# 01_MCU_Interface.net
KiCad netlist of a schematic drawn in Altium Designer
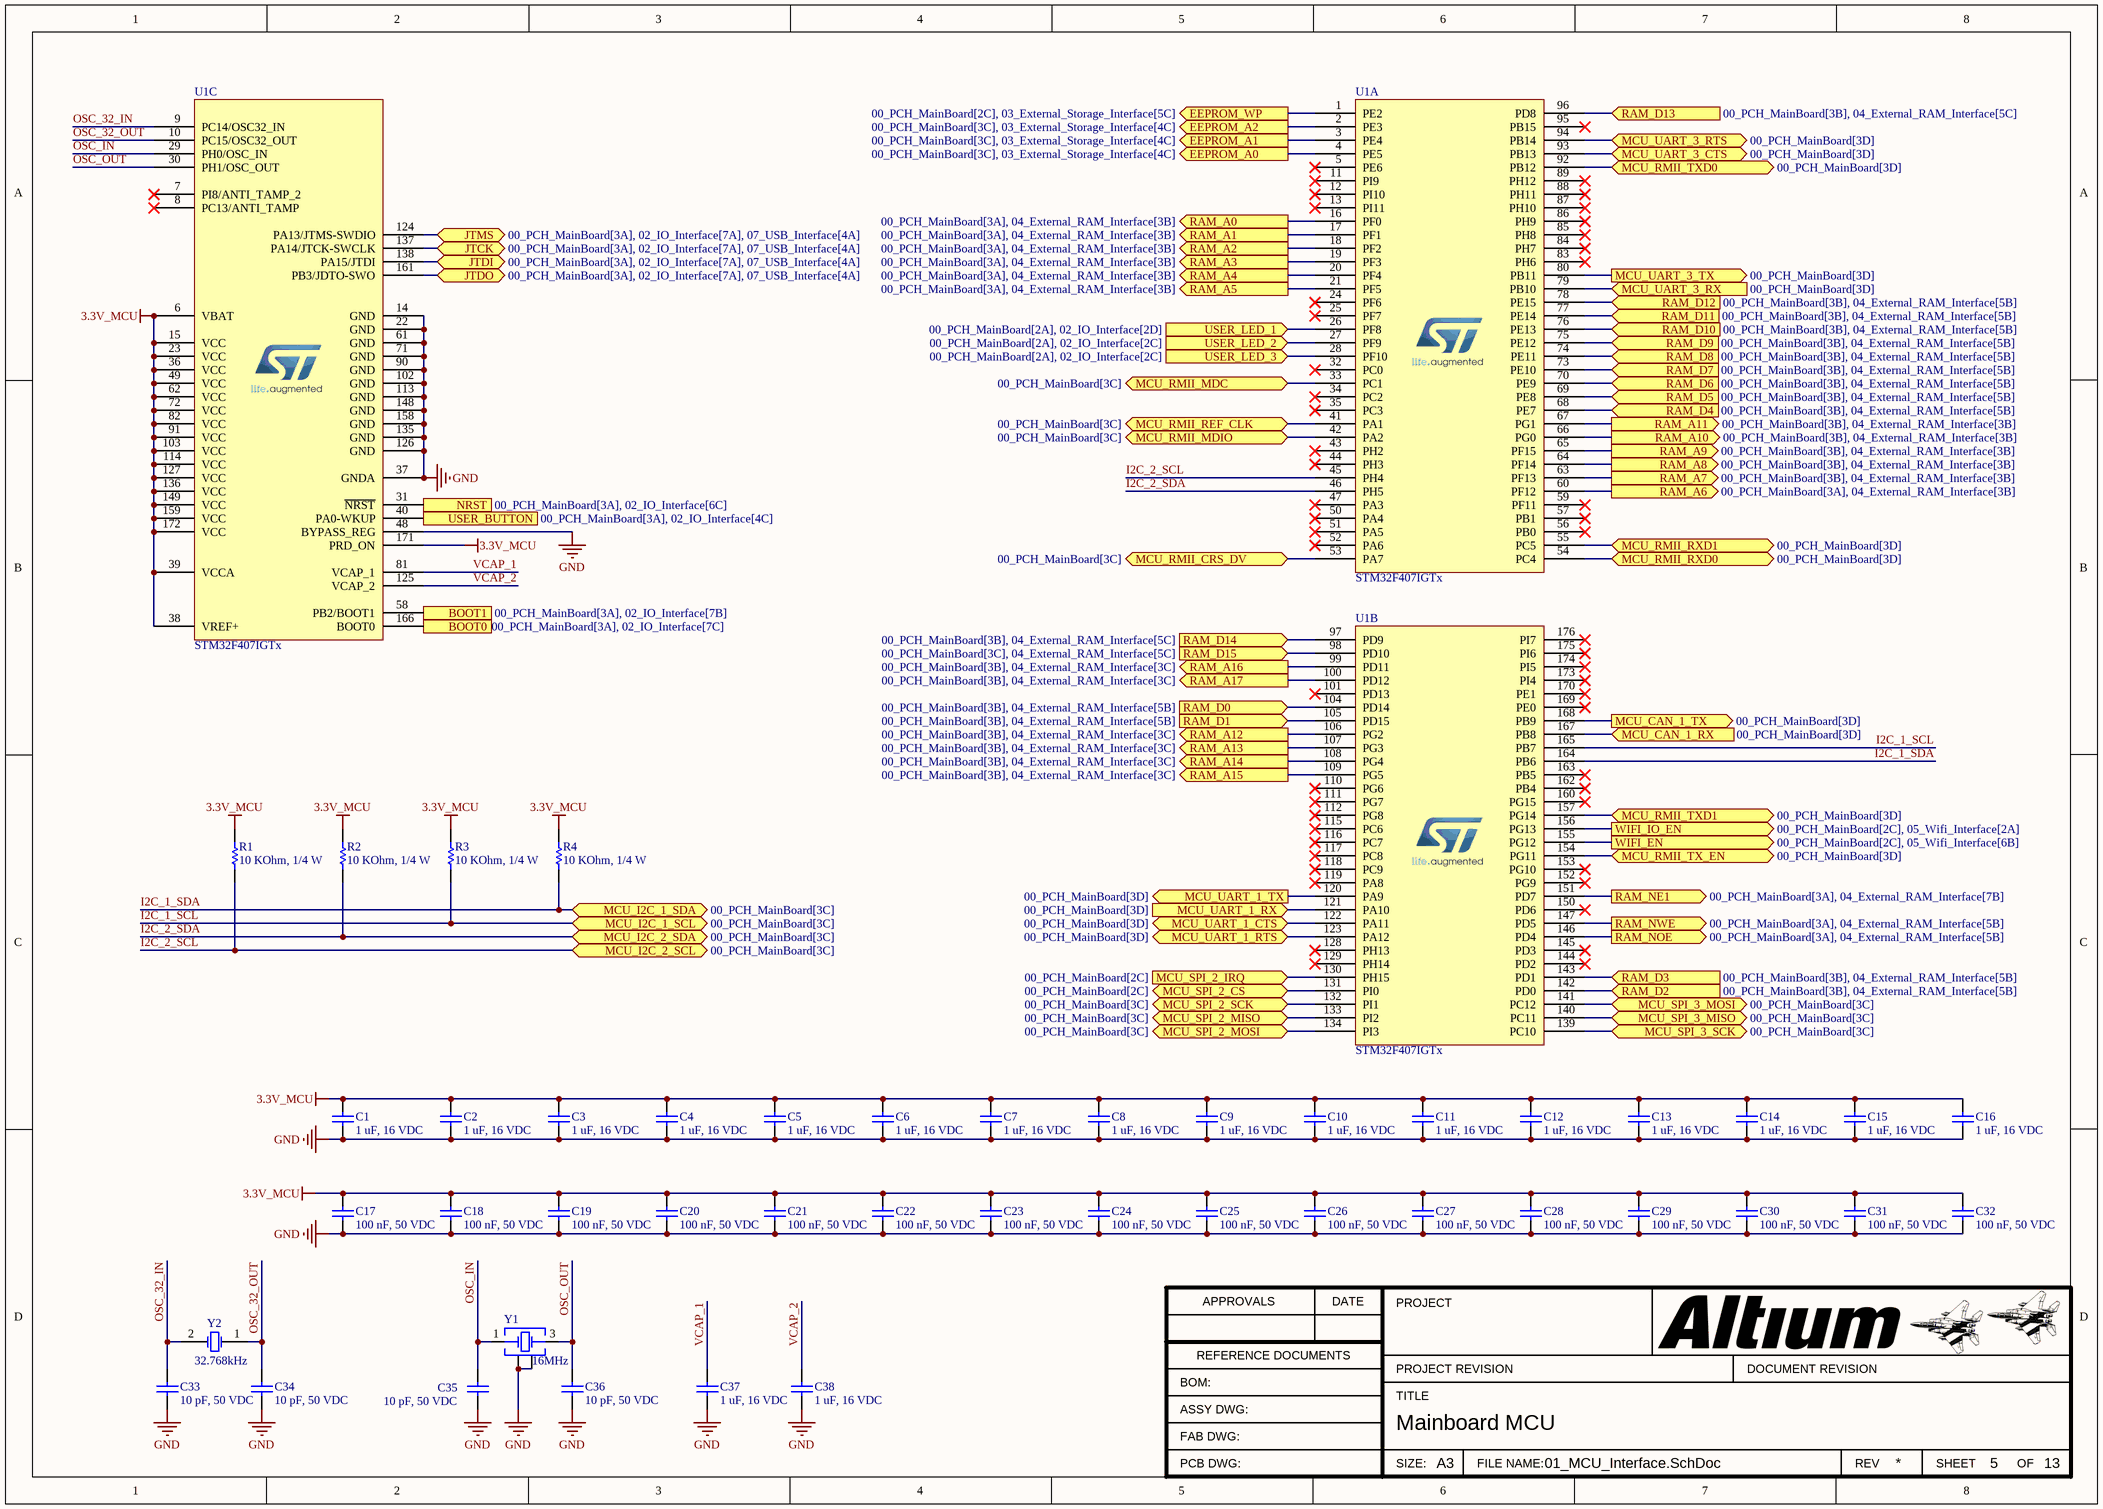
[diagram p0: 01_MCU_Interface.SchDoc]

(export (version "E")
  (design (tool "Eeschema 10.0.6"))
  (components
    (comp (ref "C1")
      (value "1 uF, 16 VDC")
      (footprint "CAP_0603")
      (description "CAP, size 0603, 1 uF, 16 VDC")
      (fields (field (name "TOLERANCE") "+/-10%"))
      (libsource (lib "Altium_Ceramic_Cap") (part "0106031051016"))
    )
    (comp (ref "C2")
      (value "1 uF, 16 VDC")
      (footprint "CAP_0603")
      (description "CAP, size 0603, 1 uF, 16 VDC")
      (fields (field (name "TOLERANCE") "+/-10%"))
      (libsource (lib "Altium_Ceramic_Cap") (part "0106031051016"))
    )
    (comp (ref "C3")
      (value "1 uF, 16 VDC")
      (footprint "CAP_0603")
      (description "CAP, size 0603, 1 uF, 16 VDC")
      (fields (field (name "TOLERANCE") "+/-10%"))
      (libsource (lib "Altium_Ceramic_Cap") (part "0106031051016"))
    )
    (comp (ref "C4")
      (value "1 uF, 16 VDC")
      (footprint "CAP_0603")
      (description "CAP, size 0603, 1 uF, 16 VDC")
      (fields (field (name "TOLERANCE") "+/-10%"))
      (libsource (lib "Altium_Ceramic_Cap") (part "0106031051016"))
    )
    (comp (ref "C5")
      (value "1 uF, 16 VDC")
      (footprint "CAP_0603")
      (description "CAP, size 0603, 1 uF, 16 VDC")
      (fields (field (name "TOLERANCE") "+/-10%"))
      (libsource (lib "Altium_Ceramic_Cap") (part "0106031051016"))
    )
    (comp (ref "C6")
      (value "1 uF, 16 VDC")
      (footprint "CAP_0603")
      (description "CAP, size 0603, 1 uF, 16 VDC")
      (fields (field (name "TOLERANCE") "+/-10%"))
      (libsource (lib "Altium_Ceramic_Cap") (part "0106031051016"))
    )
    (comp (ref "C7")
      (value "1 uF, 16 VDC")
      (footprint "CAP_0603")
      (description "CAP, size 0603, 1 uF, 16 VDC")
      (fields (field (name "TOLERANCE") "+/-10%"))
      (libsource (lib "Altium_Ceramic_Cap") (part "0106031051016"))
    )
    (comp (ref "C8")
      (value "1 uF, 16 VDC")
      (footprint "CAP_0603")
      (description "CAP, size 0603, 1 uF, 16 VDC")
      (fields (field (name "TOLERANCE") "+/-10%"))
      (libsource (lib "Altium_Ceramic_Cap") (part "0106031051016"))
    )
    (comp (ref "C9")
      (value "1 uF, 16 VDC")
      (footprint "CAP_0603")
      (description "CAP, size 0603, 1 uF, 16 VDC")
      (fields (field (name "TOLERANCE") "+/-10%"))
      (libsource (lib "Altium_Ceramic_Cap") (part "0106031051016"))
    )
    (comp (ref "C10")
      (value "1 uF, 16 VDC")
      (footprint "CAP_0603")
      (description "CAP, size 0603, 1 uF, 16 VDC")
      (fields (field (name "TOLERANCE") "+/-10%"))
      (libsource (lib "Altium_Ceramic_Cap") (part "0106031051016"))
    )
    (comp (ref "C11")
      (value "1 uF, 16 VDC")
      (footprint "CAP_0603")
      (description "CAP, size 0603, 1 uF, 16 VDC")
      (fields (field (name "TOLERANCE") "+/-10%"))
      (libsource (lib "Altium_Ceramic_Cap") (part "0106031051016"))
    )
    (comp (ref "C12")
      (value "1 uF, 16 VDC")
      (footprint "CAP_0603")
      (description "CAP, size 0603, 1 uF, 16 VDC")
      (fields (field (name "TOLERANCE") "+/-10%"))
      (libsource (lib "Altium_Ceramic_Cap") (part "0106031051016"))
    )
    (comp (ref "C13")
      (value "1 uF, 16 VDC")
      (footprint "CAP_0603")
      (description "CAP, size 0603, 1 uF, 16 VDC")
      (fields (field (name "TOLERANCE") "+/-10%"))
      (libsource (lib "Altium_Ceramic_Cap") (part "0106031051016"))
    )
    (comp (ref "C14")
      (value "1 uF, 16 VDC")
      (footprint "CAP_0603")
      (description "CAP, size 0603, 1 uF, 16 VDC")
      (fields (field (name "TOLERANCE") "+/-10%"))
      (libsource (lib "Altium_Ceramic_Cap") (part "0106031051016"))
    )
    (comp (ref "C15")
      (value "1 uF, 16 VDC")
      (footprint "CAP_0603")
      (description "CAP, size 0603, 1 uF, 16 VDC")
      (fields (field (name "TOLERANCE") "+/-10%"))
      (libsource (lib "Altium_Ceramic_Cap") (part "0106031051016"))
    )
    (comp (ref "C16")
      (value "1 uF, 16 VDC")
      (footprint "CAP_0603")
      (description "CAP, size 0603, 1 uF, 16 VDC")
      (fields (field (name "TOLERANCE") "+/-10%"))
      (libsource (lib "Altium_Ceramic_Cap") (part "0106031051016"))
    )
    (comp (ref "C17")
      (value "100 nF, 50 VDC")
      (footprint "CAP_0603")
      (description "CAP, size 0603, 100 nF, 50 VDC")
      (fields (field (name "TOLERANCE") "+/-10%"))
      (libsource (lib "Altium_Ceramic_Cap") (part "0106031041050"))
    )
    (comp (ref "C18")
      (value "100 nF, 50 VDC")
      (footprint "CAP_0603")
      (description "CAP, size 0603, 100 nF, 50 VDC")
      (fields (field (name "TOLERANCE") "+/-10%"))
      (libsource (lib "Altium_Ceramic_Cap") (part "0106031041050"))
    )
    (comp (ref "C19")
      (value "100 nF, 50 VDC")
      (footprint "CAP_0603")
      (description "CAP, size 0603, 100 nF, 50 VDC")
      (fields (field (name "TOLERANCE") "+/-10%"))
      (libsource (lib "Altium_Ceramic_Cap") (part "0106031041050"))
    )
    (comp (ref "C20")
      (value "100 nF, 50 VDC")
      (footprint "CAP_0603")
      (description "CAP, size 0603, 100 nF, 50 VDC")
      (fields (field (name "TOLERANCE") "+/-10%"))
      (libsource (lib "Altium_Ceramic_Cap") (part "0106031041050"))
    )
    (comp (ref "C21")
      (value "100 nF, 50 VDC")
      (footprint "CAP_0603")
      (description "CAP, size 0603, 100 nF, 50 VDC")
      (fields (field (name "TOLERANCE") "+/-10%"))
      (libsource (lib "Altium_Ceramic_Cap") (part "0106031041050"))
    )
    (comp (ref "C22")
      (value "100 nF, 50 VDC")
      (footprint "CAP_0603")
      (description "CAP, size 0603, 100 nF, 50 VDC")
      (fields (field (name "TOLERANCE") "+/-10%"))
      (libsource (lib "Altium_Ceramic_Cap") (part "0106031041050"))
    )
    (comp (ref "C23")
      (value "100 nF, 50 VDC")
      (footprint "CAP_0603")
      (description "CAP, size 0603, 100 nF, 50 VDC")
      (fields (field (name "TOLERANCE") "+/-10%"))
      (libsource (lib "Altium_Ceramic_Cap") (part "0106031041050"))
    )
    (comp (ref "C24")
      (value "100 nF, 50 VDC")
      (footprint "CAP_0603")
      (description "CAP, size 0603, 100 nF, 50 VDC")
      (fields (field (name "TOLERANCE") "+/-10%"))
      (libsource (lib "Altium_Ceramic_Cap") (part "0106031041050"))
    )
    (comp (ref "C25")
      (value "100 nF, 50 VDC")
      (footprint "CAP_0603")
      (description "CAP, size 0603, 100 nF, 50 VDC")
      (fields (field (name "TOLERANCE") "+/-10%"))
      (libsource (lib "Altium_Ceramic_Cap") (part "0106031041050"))
    )
    (comp (ref "C26")
      (value "100 nF, 50 VDC")
      (footprint "CAP_0603")
      (description "CAP, size 0603, 100 nF, 50 VDC")
      (fields (field (name "TOLERANCE") "+/-10%"))
      (libsource (lib "Altium_Ceramic_Cap") (part "0106031041050"))
    )
    (comp (ref "C27")
      (value "100 nF, 50 VDC")
      (footprint "CAP_0603")
      (description "CAP, size 0603, 100 nF, 50 VDC")
      (fields (field (name "TOLERANCE") "+/-10%"))
      (libsource (lib "Altium_Ceramic_Cap") (part "0106031041050"))
    )
    (comp (ref "C28")
      (value "100 nF, 50 VDC")
      (footprint "CAP_0603")
      (description "CAP, size 0603, 100 nF, 50 VDC")
      (fields (field (name "TOLERANCE") "+/-10%"))
      (libsource (lib "Altium_Ceramic_Cap") (part "0106031041050"))
    )
    (comp (ref "C29")
      (value "100 nF, 50 VDC")
      (footprint "CAP_0603")
      (description "CAP, size 0603, 100 nF, 50 VDC")
      (fields (field (name "TOLERANCE") "+/-10%"))
      (libsource (lib "Altium_Ceramic_Cap") (part "0106031041050"))
    )
    (comp (ref "C30")
      (value "100 nF, 50 VDC")
      (footprint "CAP_0603")
      (description "CAP, size 0603, 100 nF, 50 VDC")
      (fields (field (name "TOLERANCE") "+/-10%"))
      (libsource (lib "Altium_Ceramic_Cap") (part "0106031041050"))
    )
    (comp (ref "C31")
      (value "100 nF, 50 VDC")
      (footprint "CAP_0603")
      (description "CAP, size 0603, 100 nF, 50 VDC")
      (fields (field (name "TOLERANCE") "+/-10%"))
      (libsource (lib "Altium_Ceramic_Cap") (part "0106031041050"))
    )
    (comp (ref "C32")
      (value "100 nF, 50 VDC")
      (footprint "CAP_0603")
      (description "CAP, size 0603, 100 nF, 50 VDC")
      (fields (field (name "TOLERANCE") "+/-10%"))
      (libsource (lib "Altium_Ceramic_Cap") (part "0106031041050"))
    )
    (comp (ref "C33")
      (value "10 pF, 50 VDC")
      (footprint "CAP_0603")
      (description "CAP, size 0603, 10 pF, 50 VDC")
      (fields (field (name "TOLERANCE") "+/-5%"))
      (libsource (lib "Altium_Ceramic_Cap") (part "0106031000550"))
    )
    (comp (ref "C34")
      (value "10 pF, 50 VDC")
      (footprint "CAP_0603")
      (description "CAP, size 0603, 10 pF, 50 VDC")
      (fields (field (name "TOLERANCE") "+/-5%"))
      (libsource (lib "Altium_Ceramic_Cap") (part "0106031000550"))
    )
    (comp (ref "C35")
      (value "10 pF, 50 VDC")
      (footprint "CAP_0603")
      (description "CAP, size 0603, 10 pF, 50 VDC")
      (fields (field (name "TOLERANCE") "+/-5%"))
      (libsource (lib "Altium_Ceramic_Cap") (part "0106031000550"))
    )
    (comp (ref "C36")
      (value "10 pF, 50 VDC")
      (footprint "CAP_0603")
      (description "CAP, size 0603, 10 pF, 50 VDC")
      (fields (field (name "TOLERANCE") "+/-5%"))
      (libsource (lib "Altium_Ceramic_Cap") (part "0106031000550"))
    )
    (comp (ref "C37")
      (value "1 uF, 16 VDC")
      (footprint "CAP_0603")
      (description "CAP, size 0603, 1 uF, 16 VDC")
      (fields (field (name "TOLERANCE") "+/-10%"))
      (libsource (lib "Altium_Ceramic_Cap") (part "0106031051016"))
    )
    (comp (ref "C38")
      (value "1 uF, 16 VDC")
      (footprint "CAP_0603")
      (description "CAP, size 0603, 1 uF, 16 VDC")
      (fields (field (name "TOLERANCE") "+/-10%"))
      (libsource (lib "Altium_Ceramic_Cap") (part "0106031051016"))
    )
    (comp (ref "R1")
      (value "10 KOhm, 1/4 W")
      (footprint "resistor_0603")
      (description "RES, size 0603, 10 KOhm, 1/4 W")
      (libsource (lib "Altium_Resistor") (part "0006031031"))
    )
    (comp (ref "R2")
      (value "10 KOhm, 1/4 W")
      (footprint "resistor_0603")
      (description "RES, size 0603, 10 KOhm, 1/4 W")
      (libsource (lib "Altium_Resistor") (part "0006031031"))
    )
    (comp (ref "R3")
      (value "10 KOhm, 1/4 W")
      (footprint "resistor_0603")
      (description "RES, size 0603, 10 KOhm, 1/4 W")
      (libsource (lib "Altium_Resistor") (part "0006031031"))
    )
    (comp (ref "R4")
      (value "10 KOhm, 1/4 W")
      (footprint "resistor_0603")
      (description "RES, size 0603, 10 KOhm, 1/4 W")
      (libsource (lib "Altium_Resistor") (part "0006031031"))
    )
    (comp (ref "U1")
      (value "STM32F407IGTx")
      (footprint "STM32F407IGTx")
      (description "ARM Microcontrollers - MCU ARM M4 1024 FLASH 168 Mhz 192kB SRAM")
      (fields (field (name "MANUFACTURER") "STM"))
      (libsource (lib "Altium_MCU") (part "STM32F407IGTx"))
    )
    (comp (ref "Y1")
      (value "16MHz")
      (footprint "WE-XTAL_CFPX-180")
      (description "WE-XTAL Quartz Crystal, SMT, CFPX-180, 16MHz, +/-20ppm")
      (fields
        (field (name "MANUFACTURER PART NUMBER") "NX3225SA-16.000M-STD-CRS-2")
        (field (name "MANUFACTURER") "NDK")
      )
      (libsource (lib "Altium_XTAL") (part "073525166008"))
    )
    (comp (ref "Y2")
      (value "32.768kHz")
      (footprint "WE-XTAL_WATCH_830002995B")
      (description "WE-XTAL Watch Crystal, THT, WATCH, 32.768kHz, +/-20ppm")
      (fields
        (field (name "MANUFACTURER PART NUMBER") "830002995B")
        (field (name "MANUFACTURER") "Wurth Elektronik")
      )
      (libsource (lib "Altium_XTAL") (part "070003323012"))
    )
  )
  (nets
    (net (code "1") (name "/BOOT0") (class "Default")
      (node (ref "U1") (pin "166") (pinfunction "BOOT0_166") (pintype "passive"))
    )
    (net (code "2") (name "/BOOT1") (class "Default")
      (node (ref "U1") (pin "58") (pinfunction "PB2/BOOT1_58") (pintype "passive"))
    )
    (net (code "3") (name "/EEPROM_A0") (class "Default")
      (node (ref "U1") (pin "4") (pinfunction "PE5_4") (pintype "passive"))
    )
    (net (code "4") (name "/EEPROM_A1") (class "Default")
      (node (ref "U1") (pin "3") (pinfunction "PE4_3") (pintype "passive"))
    )
    (net (code "5") (name "/EEPROM_A2") (class "Default")
      (node (ref "U1") (pin "2") (pinfunction "PE3_2") (pintype "passive"))
    )
    (net (code "6") (name "/EEPROM_WP") (class "Default")
      (node (ref "U1") (pin "1") (pinfunction "PE2_1") (pintype "passive"))
    )
    (net (code "7") (name "/I2C_1_SCL") (class "Default")
      (node (ref "R3") (pin "1") (pinfunction "1_1") (pintype "passive"))
      (node (ref "U1") (pin "165") (pinfunction "PB7_165") (pintype "passive"))
    )
    (net (code "8") (name "/I2C_1_SDA") (class "Default")
      (node (ref "R4") (pin "1") (pinfunction "1_1") (pintype "passive"))
      (node (ref "U1") (pin "164") (pinfunction "PB6_164") (pintype "passive"))
    )
    (net (code "9") (name "/I2C_2_SCL") (class "Default")
      (node (ref "R1") (pin "1") (pinfunction "1_1") (pintype "passive"))
      (node (ref "U1") (pin "45") (pinfunction "PH4_45") (pintype "passive"))
    )
    (net (code "10") (name "/I2C_2_SDA") (class "Default")
      (node (ref "R2") (pin "1") (pinfunction "1_1") (pintype "passive"))
      (node (ref "U1") (pin "46") (pinfunction "PH5_46") (pintype "passive"))
    )
    (net (code "11") (name "/JTCK") (class "Default")
      (node (ref "U1") (pin "137") (pinfunction "PA14/JTCK-SWCLK_137") (pintype "passive"))
    )
    (net (code "12") (name "/JTDI") (class "Default")
      (node (ref "U1") (pin "138") (pinfunction "PA15/JTDI_138") (pintype "passive"))
    )
    (net (code "13") (name "/JTDO") (class "Default")
      (node (ref "U1") (pin "161") (pinfunction "PB3/JDTO-SWO_161") (pintype "passive"))
    )
    (net (code "14") (name "/JTMS") (class "Default")
      (node (ref "U1") (pin "124") (pinfunction "PA13/JTMS-SWDIO_124") (pintype "passive"))
    )
    (net (code "15") (name "/MCU_CAN_1_RX") (class "Default")
      (node (ref "U1") (pin "167") (pinfunction "PB8_167") (pintype "passive"))
    )
    (net (code "16") (name "/MCU_CAN_1_TX") (class "Default")
      (node (ref "U1") (pin "168") (pinfunction "PB9_168") (pintype "passive"))
    )
    (net (code "17") (name "/MCU_RMII_CRS_DV") (class "Default")
      (node (ref "U1") (pin "53") (pinfunction "PA7_53") (pintype "passive"))
    )
    (net (code "18") (name "/MCU_RMII_MDC") (class "Default")
      (node (ref "U1") (pin "33") (pinfunction "PC1_33") (pintype "passive"))
    )
    (net (code "19") (name "/MCU_RMII_MDIO") (class "Default")
      (node (ref "U1") (pin "42") (pinfunction "PA2_42") (pintype "passive"))
    )
    (net (code "20") (name "/MCU_RMII_REF_CLK") (class "Default")
      (node (ref "U1") (pin "41") (pinfunction "PA1_41") (pintype "passive"))
    )
    (net (code "21") (name "/MCU_RMII_RXD0") (class "Default")
      (node (ref "U1") (pin "54") (pinfunction "PC4_54") (pintype "passive"))
    )
    (net (code "22") (name "/MCU_RMII_RXD1") (class "Default")
      (node (ref "U1") (pin "55") (pinfunction "PC5_55") (pintype "passive"))
    )
    (net (code "23") (name "/MCU_RMII_TXD0") (class "Default")
      (node (ref "U1") (pin "92") (pinfunction "PB12_92") (pintype "passive"))
    )
    (net (code "24") (name "/MCU_RMII_TXD1") (class "Default")
      (node (ref "U1") (pin "157") (pinfunction "PG14_157") (pintype "passive"))
    )
    (net (code "25") (name "/MCU_RMII_TX_EN") (class "Default")
      (node (ref "U1") (pin "154") (pinfunction "PG11_154") (pintype "passive"))
    )
    (net (code "26") (name "/MCU_SPI_2_CS") (class "Default")
      (node (ref "U1") (pin "131") (pinfunction "PI0_131") (pintype "passive"))
    )
    (net (code "27") (name "/MCU_SPI_2_IRQ") (class "Default")
      (node (ref "U1") (pin "130") (pinfunction "PH15_130") (pintype "passive"))
    )
    (net (code "28") (name "/MCU_SPI_2_MISO") (class "Default")
      (node (ref "U1") (pin "133") (pinfunction "PI2_133") (pintype "passive"))
    )
    (net (code "29") (name "/MCU_SPI_2_MOSI") (class "Default")
      (node (ref "U1") (pin "134") (pinfunction "PI3_134") (pintype "passive"))
    )
    (net (code "30") (name "/MCU_SPI_2_SCK") (class "Default")
      (node (ref "U1") (pin "132") (pinfunction "PI1_132") (pintype "passive"))
    )
    (net (code "31") (name "/MCU_SPI_3_MISO") (class "Default")
      (node (ref "U1") (pin "140") (pinfunction "PC11_140") (pintype "passive"))
    )
    (net (code "32") (name "/MCU_SPI_3_MOSI") (class "Default")
      (node (ref "U1") (pin "141") (pinfunction "PC12_141") (pintype "passive"))
    )
    (net (code "33") (name "/MCU_SPI_3_SCK") (class "Default")
      (node (ref "U1") (pin "139") (pinfunction "PC10_139") (pintype "passive"))
    )
    (net (code "34") (name "/MCU_UART_1_CTS") (class "Default")
      (node (ref "U1") (pin "122") (pinfunction "PA11_122") (pintype "passive"))
    )
    (net (code "35") (name "/MCU_UART_1_RTS") (class "Default")
      (node (ref "U1") (pin "123") (pinfunction "PA12_123") (pintype "passive"))
    )
    (net (code "36") (name "/MCU_UART_1_RX") (class "Default")
      (node (ref "U1") (pin "121") (pinfunction "PA10_121") (pintype "passive"))
    )
    (net (code "37") (name "/MCU_UART_1_TX") (class "Default")
      (node (ref "U1") (pin "120") (pinfunction "PA9_120") (pintype "passive"))
    )
    (net (code "38") (name "/MCU_UART_3_CTS") (class "Default")
      (node (ref "U1") (pin "93") (pinfunction "PB13_93") (pintype "passive"))
    )
    (net (code "39") (name "/MCU_UART_3_RTS") (class "Default")
      (node (ref "U1") (pin "94") (pinfunction "PB14_94") (pintype "passive"))
    )
    (net (code "40") (name "/MCU_UART_3_RX") (class "Default")
      (node (ref "U1") (pin "79") (pinfunction "PB10_79") (pintype "passive"))
    )
    (net (code "41") (name "/MCU_UART_3_TX") (class "Default")
      (node (ref "U1") (pin "80") (pinfunction "PB11_80") (pintype "passive"))
    )
    (net (code "42") (name "/NRST") (class "Default")
      (node (ref "U1") (pin "31") (pinfunction "~{NRST}_31") (pintype "passive"))
    )
    (net (code "43") (name "/OSC_32_IN") (class "Default")
      (node (ref "C33") (pin "2") (pinfunction "2_2") (pintype "passive"))
      (node (ref "U1") (pin "9") (pinfunction "PC14/OSC32_IN_9") (pintype "passive"))
      (node (ref "Y2") (pin "2") (pinfunction "OSC2_2") (pintype "passive"))
    )
    (net (code "44") (name "/OSC_32_OUT") (class "Default")
      (node (ref "C34") (pin "2") (pinfunction "2_2") (pintype "passive"))
      (node (ref "U1") (pin "10") (pinfunction "PC15/OSC32_OUT_10") (pintype "passive"))
      (node (ref "Y2") (pin "1") (pinfunction "OSC1_1") (pintype "passive"))
    )
    (net (code "45") (name "/OSC_IN") (class "Default")
      (node (ref "C35") (pin "2") (pinfunction "2_2") (pintype "passive"))
      (node (ref "U1") (pin "29") (pinfunction "PH0/OSC_IN_29") (pintype "passive"))
      (node (ref "Y1") (pin "1") (pinfunction "Crystal_1") (pintype "passive"))
    )
    (net (code "46") (name "/OSC_OUT") (class "Default")
      (node (ref "C36") (pin "2") (pinfunction "2_2") (pintype "passive"))
      (node (ref "U1") (pin "30") (pinfunction "PH1/OSC_OUT_30") (pintype "passive"))
      (node (ref "Y1") (pin "3") (pinfunction "Crystal_3") (pintype "passive"))
    )
    (net (code "47") (name "/RAM_A0") (class "Default")
      (node (ref "U1") (pin "16") (pinfunction "PF0_16") (pintype "passive"))
    )
    (net (code "48") (name "/RAM_A1") (class "Default")
      (node (ref "U1") (pin "17") (pinfunction "PF1_17") (pintype "passive"))
    )
    (net (code "49") (name "/RAM_A2") (class "Default")
      (node (ref "U1") (pin "18") (pinfunction "PF2_18") (pintype "passive"))
    )
    (net (code "50") (name "/RAM_A3") (class "Default")
      (node (ref "U1") (pin "19") (pinfunction "PF3_19") (pintype "passive"))
    )
    (net (code "51") (name "/RAM_A4") (class "Default")
      (node (ref "U1") (pin "20") (pinfunction "PF4_20") (pintype "passive"))
    )
    (net (code "52") (name "/RAM_A5") (class "Default")
      (node (ref "U1") (pin "21") (pinfunction "PF5_21") (pintype "passive"))
    )
    (net (code "53") (name "/RAM_A6") (class "Default")
      (node (ref "U1") (pin "60") (pinfunction "PF12_60") (pintype "passive"))
    )
    (net (code "54") (name "/RAM_A7") (class "Default")
      (node (ref "U1") (pin "63") (pinfunction "PF13_63") (pintype "passive"))
    )
    (net (code "55") (name "/RAM_A8") (class "Default")
      (node (ref "U1") (pin "64") (pinfunction "PF14_64") (pintype "passive"))
    )
    (net (code "56") (name "/RAM_A9") (class "Default")
      (node (ref "U1") (pin "65") (pinfunction "PF15_65") (pintype "passive"))
    )
    (net (code "57") (name "/RAM_A10") (class "Default")
      (node (ref "U1") (pin "66") (pinfunction "PG0_66") (pintype "passive"))
    )
    (net (code "58") (name "/RAM_A11") (class "Default")
      (node (ref "U1") (pin "67") (pinfunction "PG1_67") (pintype "passive"))
    )
    (net (code "59") (name "/RAM_A12") (class "Default")
      (node (ref "U1") (pin "106") (pinfunction "PG2_106") (pintype "passive"))
    )
    (net (code "60") (name "/RAM_A13") (class "Default")
      (node (ref "U1") (pin "107") (pinfunction "PG3_107") (pintype "passive"))
    )
    (net (code "61") (name "/RAM_A14") (class "Default")
      (node (ref "U1") (pin "108") (pinfunction "PG4_108") (pintype "passive"))
    )
    (net (code "62") (name "/RAM_A15") (class "Default")
      (node (ref "U1") (pin "109") (pinfunction "PG5_109") (pintype "passive"))
    )
    (net (code "63") (name "/RAM_A16") (class "Default")
      (node (ref "U1") (pin "99") (pinfunction "PD11_99") (pintype "passive"))
    )
    (net (code "64") (name "/RAM_A17") (class "Default")
      (node (ref "U1") (pin "100") (pinfunction "PD12_100") (pintype "passive"))
    )
    (net (code "65") (name "/RAM_D0") (class "Default")
      (node (ref "U1") (pin "104") (pinfunction "PD14_104") (pintype "passive"))
    )
    (net (code "66") (name "/RAM_D1") (class "Default")
      (node (ref "U1") (pin "105") (pinfunction "PD15_105") (pintype "passive"))
    )
    (net (code "67") (name "/RAM_D2") (class "Default")
      (node (ref "U1") (pin "142") (pinfunction "PD0_142") (pintype "passive"))
    )
    (net (code "68") (name "/RAM_D3") (class "Default")
      (node (ref "U1") (pin "143") (pinfunction "PD1_143") (pintype "passive"))
    )
    (net (code "69") (name "/RAM_D4") (class "Default")
      (node (ref "U1") (pin "68") (pinfunction "PE7_68") (pintype "passive"))
    )
    (net (code "70") (name "/RAM_D5") (class "Default")
      (node (ref "U1") (pin "69") (pinfunction "PE8_69") (pintype "passive"))
    )
    (net (code "71") (name "/RAM_D6") (class "Default")
      (node (ref "U1") (pin "70") (pinfunction "PE9_70") (pintype "passive"))
    )
    (net (code "72") (name "/RAM_D7") (class "Default")
      (node (ref "U1") (pin "73") (pinfunction "PE10_73") (pintype "passive"))
    )
    (net (code "73") (name "/RAM_D8") (class "Default")
      (node (ref "U1") (pin "74") (pinfunction "PE11_74") (pintype "passive"))
    )
    (net (code "74") (name "/RAM_D9") (class "Default")
      (node (ref "U1") (pin "75") (pinfunction "PE12_75") (pintype "passive"))
    )
    (net (code "75") (name "/RAM_D10") (class "Default")
      (node (ref "U1") (pin "76") (pinfunction "PE13_76") (pintype "passive"))
    )
    (net (code "76") (name "/RAM_D11") (class "Default")
      (node (ref "U1") (pin "77") (pinfunction "PE14_77") (pintype "passive"))
    )
    (net (code "77") (name "/RAM_D12") (class "Default")
      (node (ref "U1") (pin "78") (pinfunction "PE15_78") (pintype "passive"))
    )
    (net (code "78") (name "/RAM_D13") (class "Default")
      (node (ref "U1") (pin "96") (pinfunction "PD8_96") (pintype "passive"))
    )
    (net (code "79") (name "/RAM_D14") (class "Default")
      (node (ref "U1") (pin "97") (pinfunction "PD9_97") (pintype "passive"))
    )
    (net (code "80") (name "/RAM_D15") (class "Default")
      (node (ref "U1") (pin "98") (pinfunction "PD10_98") (pintype "passive"))
    )
    (net (code "81") (name "/RAM_NE1") (class "Default")
      (node (ref "U1") (pin "151") (pinfunction "PD7_151") (pintype "passive"))
    )
    (net (code "82") (name "/RAM_NOE") (class "Default")
      (node (ref "U1") (pin "146") (pinfunction "PD4_146") (pintype "passive"))
    )
    (net (code "83") (name "/RAM_NWE") (class "Default")
      (node (ref "U1") (pin "147") (pinfunction "PD5_147") (pintype "passive"))
    )
    (net (code "84") (name "/USER_BUTTON") (class "Default")
      (node (ref "U1") (pin "40") (pinfunction "PA0-WKUP_40") (pintype "passive"))
    )
    (net (code "85") (name "/USER_LED_1") (class "Default")
      (node (ref "U1") (pin "26") (pinfunction "PF8_26") (pintype "passive"))
    )
    (net (code "86") (name "/USER_LED_2") (class "Default")
      (node (ref "U1") (pin "27") (pinfunction "PF9_27") (pintype "passive"))
    )
    (net (code "87") (name "/USER_LED_3") (class "Default")
      (node (ref "U1") (pin "28") (pinfunction "PF10_28") (pintype "passive"))
    )
    (net (code "88") (name "/VCAP_1") (class "Default")
      (node (ref "C37") (pin "2") (pinfunction "2_2") (pintype "passive"))
      (node (ref "U1") (pin "81") (pinfunction "VCAP_1_81") (pintype "passive"))
    )
    (net (code "89") (name "/VCAP_2") (class "Default")
      (node (ref "C38") (pin "2") (pinfunction "2_2") (pintype "passive"))
      (node (ref "U1") (pin "125") (pinfunction "VCAP_2_125") (pintype "passive"))
    )
    (net (code "90") (name "/WIFI_EN") (class "Default")
      (node (ref "U1") (pin "155") (pinfunction "PG12_155") (pintype "passive"))
    )
    (net (code "91") (name "/WIFI_IO_EN") (class "Default")
      (node (ref "U1") (pin "156") (pinfunction "PG13_156") (pintype "passive"))
    )
    (net (code "92") (name "3.3V_MCU") (class "Default")
      (node (ref "C1") (pin "2") (pinfunction "2_2") (pintype "passive"))
      (node (ref "C10") (pin "2") (pinfunction "2_2") (pintype "passive"))
      (node (ref "C11") (pin "2") (pinfunction "2_2") (pintype "passive"))
      (node (ref "C12") (pin "2") (pinfunction "2_2") (pintype "passive"))
      (node (ref "C13") (pin "2") (pinfunction "2_2") (pintype "passive"))
      (node (ref "C14") (pin "2") (pinfunction "2_2") (pintype "passive"))
      (node (ref "C15") (pin "2") (pinfunction "2_2") (pintype "passive"))
      (node (ref "C16") (pin "2") (pinfunction "2_2") (pintype "passive"))
      (node (ref "C17") (pin "2") (pinfunction "2_2") (pintype "passive"))
      (node (ref "C18") (pin "2") (pinfunction "2_2") (pintype "passive"))
      (node (ref "C19") (pin "2") (pinfunction "2_2") (pintype "passive"))
      (node (ref "C2") (pin "2") (pinfunction "2_2") (pintype "passive"))
      (node (ref "C20") (pin "2") (pinfunction "2_2") (pintype "passive"))
      (node (ref "C21") (pin "2") (pinfunction "2_2") (pintype "passive"))
      (node (ref "C22") (pin "2") (pinfunction "2_2") (pintype "passive"))
      (node (ref "C23") (pin "2") (pinfunction "2_2") (pintype "passive"))
      (node (ref "C24") (pin "2") (pinfunction "2_2") (pintype "passive"))
      (node (ref "C25") (pin "2") (pinfunction "2_2") (pintype "passive"))
      (node (ref "C26") (pin "2") (pinfunction "2_2") (pintype "passive"))
      (node (ref "C27") (pin "2") (pinfunction "2_2") (pintype "passive"))
      (node (ref "C28") (pin "2") (pinfunction "2_2") (pintype "passive"))
      (node (ref "C29") (pin "2") (pinfunction "2_2") (pintype "passive"))
      (node (ref "C3") (pin "2") (pinfunction "2_2") (pintype "passive"))
      (node (ref "C30") (pin "2") (pinfunction "2_2") (pintype "passive"))
      (node (ref "C31") (pin "2") (pinfunction "2_2") (pintype "passive"))
      (node (ref "C32") (pin "2") (pinfunction "2_2") (pintype "passive"))
      (node (ref "C4") (pin "2") (pinfunction "2_2") (pintype "passive"))
      (node (ref "C5") (pin "2") (pinfunction "2_2") (pintype "passive"))
      (node (ref "C6") (pin "2") (pinfunction "2_2") (pintype "passive"))
      (node (ref "C7") (pin "2") (pinfunction "2_2") (pintype "passive"))
      (node (ref "C8") (pin "2") (pinfunction "2_2") (pintype "passive"))
      (node (ref "C9") (pin "2") (pinfunction "2_2") (pintype "passive"))
      (node (ref "R1") (pin "2") (pinfunction "2_2") (pintype "passive"))
      (node (ref "R2") (pin "2") (pinfunction "2_2") (pintype "passive"))
      (node (ref "R3") (pin "2") (pinfunction "2_2") (pintype "passive"))
      (node (ref "R4") (pin "2") (pinfunction "2_2") (pintype "passive"))
      (node (ref "U1") (pin "103") (pinfunction "VCC_103") (pintype "passive"))
      (node (ref "U1") (pin "114") (pinfunction "VCC_114") (pintype "passive"))
      (node (ref "U1") (pin "127") (pinfunction "VCC_127") (pintype "passive"))
      (node (ref "U1") (pin "136") (pinfunction "VCC_136") (pintype "passive"))
      (node (ref "U1") (pin "149") (pinfunction "VCC_149") (pintype "passive"))
      (node (ref "U1") (pin "15") (pinfunction "VCC_15") (pintype "passive"))
      (node (ref "U1") (pin "159") (pinfunction "VCC_159") (pintype "passive"))
      (node (ref "U1") (pin "171") (pinfunction "PRD_ON_171") (pintype "passive"))
      (node (ref "U1") (pin "172") (pinfunction "VCC_172") (pintype "passive"))
      (node (ref "U1") (pin "23") (pinfunction "VCC_23") (pintype "passive"))
      (node (ref "U1") (pin "36") (pinfunction "VCC_36") (pintype "passive"))
      (node (ref "U1") (pin "38") (pinfunction "VREF+_38") (pintype "passive"))
      (node (ref "U1") (pin "39") (pinfunction "VCCA_39") (pintype "passive"))
      (node (ref "U1") (pin "49") (pinfunction "VCC_49") (pintype "passive"))
      (node (ref "U1") (pin "6") (pinfunction "VBAT_6") (pintype "passive"))
      (node (ref "U1") (pin "62") (pinfunction "VCC_62") (pintype "passive"))
      (node (ref "U1") (pin "72") (pinfunction "VCC_72") (pintype "passive"))
      (node (ref "U1") (pin "82") (pinfunction "VCC_82") (pintype "passive"))
      (node (ref "U1") (pin "91") (pinfunction "VCC_91") (pintype "passive"))
    )
    (net (code "93") (name "GND") (class "Default")
      (node (ref "C1") (pin "1") (pinfunction "1_1") (pintype "passive"))
      (node (ref "C10") (pin "1") (pinfunction "1_1") (pintype "passive"))
      (node (ref "C11") (pin "1") (pinfunction "1_1") (pintype "passive"))
      (node (ref "C12") (pin "1") (pinfunction "1_1") (pintype "passive"))
      (node (ref "C13") (pin "1") (pinfunction "1_1") (pintype "passive"))
      (node (ref "C14") (pin "1") (pinfunction "1_1") (pintype "passive"))
      (node (ref "C15") (pin "1") (pinfunction "1_1") (pintype "passive"))
      (node (ref "C16") (pin "1") (pinfunction "1_1") (pintype "passive"))
      (node (ref "C17") (pin "1") (pinfunction "1_1") (pintype "passive"))
      (node (ref "C18") (pin "1") (pinfunction "1_1") (pintype "passive"))
      (node (ref "C19") (pin "1") (pinfunction "1_1") (pintype "passive"))
      (node (ref "C2") (pin "1") (pinfunction "1_1") (pintype "passive"))
      (node (ref "C20") (pin "1") (pinfunction "1_1") (pintype "passive"))
      (node (ref "C21") (pin "1") (pinfunction "1_1") (pintype "passive"))
      (node (ref "C22") (pin "1") (pinfunction "1_1") (pintype "passive"))
      (node (ref "C23") (pin "1") (pinfunction "1_1") (pintype "passive"))
      (node (ref "C24") (pin "1") (pinfunction "1_1") (pintype "passive"))
      (node (ref "C25") (pin "1") (pinfunction "1_1") (pintype "passive"))
      (node (ref "C26") (pin "1") (pinfunction "1_1") (pintype "passive"))
      (node (ref "C27") (pin "1") (pinfunction "1_1") (pintype "passive"))
      (node (ref "C28") (pin "1") (pinfunction "1_1") (pintype "passive"))
      (node (ref "C29") (pin "1") (pinfunction "1_1") (pintype "passive"))
      (node (ref "C3") (pin "1") (pinfunction "1_1") (pintype "passive"))
      (node (ref "C30") (pin "1") (pinfunction "1_1") (pintype "passive"))
      (node (ref "C31") (pin "1") (pinfunction "1_1") (pintype "passive"))
      (node (ref "C32") (pin "1") (pinfunction "1_1") (pintype "passive"))
      (node (ref "C33") (pin "1") (pinfunction "1_1") (pintype "passive"))
      (node (ref "C34") (pin "1") (pinfunction "1_1") (pintype "passive"))
      (node (ref "C35") (pin "1") (pinfunction "1_1") (pintype "passive"))
      (node (ref "C36") (pin "1") (pinfunction "1_1") (pintype "passive"))
      (node (ref "C37") (pin "1") (pinfunction "1_1") (pintype "passive"))
      (node (ref "C38") (pin "1") (pinfunction "1_1") (pintype "passive"))
      (node (ref "C4") (pin "1") (pinfunction "1_1") (pintype "passive"))
      (node (ref "C5") (pin "1") (pinfunction "1_1") (pintype "passive"))
      (node (ref "C6") (pin "1") (pinfunction "1_1") (pintype "passive"))
      (node (ref "C7") (pin "1") (pinfunction "1_1") (pintype "passive"))
      (node (ref "C8") (pin "1") (pinfunction "1_1") (pintype "passive"))
      (node (ref "C9") (pin "1") (pinfunction "1_1") (pintype "passive"))
      (node (ref "U1") (pin "102") (pinfunction "GND_102") (pintype "passive"))
      (node (ref "U1") (pin "113") (pinfunction "GND_113") (pintype "passive"))
      (node (ref "U1") (pin "126") (pinfunction "GND_126") (pintype "passive"))
      (node (ref "U1") (pin "135") (pinfunction "GND_135") (pintype "passive"))
      (node (ref "U1") (pin "14") (pinfunction "GND_14") (pintype "passive"))
      (node (ref "U1") (pin "148") (pinfunction "GND_148") (pintype "passive"))
      (node (ref "U1") (pin "158") (pinfunction "GND_158") (pintype "passive"))
      (node (ref "U1") (pin "22") (pinfunction "GND_22") (pintype "passive"))
      (node (ref "U1") (pin "37") (pinfunction "GNDA_37") (pintype "passive"))
      (node (ref "U1") (pin "48") (pinfunction "BYPASS_REG_48") (pintype "passive"))
      (node (ref "U1") (pin "61") (pinfunction "GND_61") (pintype "passive"))
      (node (ref "U1") (pin "71") (pinfunction "GND_71") (pintype "passive"))
      (node (ref "U1") (pin "90") (pinfunction "GND_90") (pintype "passive"))
      (node (ref "Y1") (pin "2") (pinfunction "GND_2") (pintype "passive"))
      (node (ref "Y1") (pin "4") (pinfunction "GND_4") (pintype "passive"))
    )
    (net (code "94") (name "unconnected-(U1A-PA3-Pad47)") (class "Default")
      (node (ref "U1") (pin "47") (pinfunction "PA3_47") (pintype "passive+no_connect"))
    )
    (net (code "95") (name "unconnected-(U1A-PA4-Pad50)") (class "Default")
      (node (ref "U1") (pin "50") (pinfunction "PA4_50") (pintype "passive+no_connect"))
    )
    (net (code "96") (name "unconnected-(U1A-PA5-Pad51)") (class "Default")
      (node (ref "U1") (pin "51") (pinfunction "PA5_51") (pintype "passive+no_connect"))
    )
    (net (code "97") (name "unconnected-(U1A-PA6-Pad52)") (class "Default")
      (node (ref "U1") (pin "52") (pinfunction "PA6_52") (pintype "passive+no_connect"))
    )
    (net (code "98") (name "unconnected-(U1A-PB0-Pad56)") (class "Default")
      (node (ref "U1") (pin "56") (pinfunction "PB0_56") (pintype "passive+no_connect"))
    )
    (net (code "99") (name "unconnected-(U1A-PB1-Pad57)") (class "Default")
      (node (ref "U1") (pin "57") (pinfunction "PB1_57") (pintype "passive+no_connect"))
    )
    (net (code "100") (name "unconnected-(U1A-PB15-Pad95)") (class "Default")
      (node (ref "U1") (pin "95") (pinfunction "PB15_95") (pintype "passive+no_connect"))
    )
    (net (code "101") (name "unconnected-(U1A-PC0-Pad32)") (class "Default")
      (node (ref "U1") (pin "32") (pinfunction "PC0_32") (pintype "passive+no_connect"))
    )
    (net (code "102") (name "unconnected-(U1A-PC2-Pad34)") (class "Default")
      (node (ref "U1") (pin "34") (pinfunction "PC2_34") (pintype "passive+no_connect"))
    )
    (net (code "103") (name "unconnected-(U1A-PC3-Pad35)") (class "Default")
      (node (ref "U1") (pin "35") (pinfunction "PC3_35") (pintype "passive+no_connect"))
    )
    (net (code "104") (name "unconnected-(U1A-PE6-Pad5)") (class "Default")
      (node (ref "U1") (pin "5") (pinfunction "PE6_5") (pintype "passive+no_connect"))
    )
    (net (code "105") (name "unconnected-(U1A-PF6-Pad24)") (class "Default")
      (node (ref "U1") (pin "24") (pinfunction "PF6_24") (pintype "passive+no_connect"))
    )
    (net (code "106") (name "unconnected-(U1A-PF7-Pad25)") (class "Default")
      (node (ref "U1") (pin "25") (pinfunction "PF7_25") (pintype "passive+no_connect"))
    )
    (net (code "107") (name "unconnected-(U1A-PF11-Pad59)") (class "Default")
      (node (ref "U1") (pin "59") (pinfunction "PF11_59") (pintype "passive+no_connect"))
    )
    (net (code "108") (name "unconnected-(U1A-PH2-Pad43)") (class "Default")
      (node (ref "U1") (pin "43") (pinfunction "PH2_43") (pintype "passive+no_connect"))
    )
    (net (code "109") (name "unconnected-(U1A-PH3-Pad44)") (class "Default")
      (node (ref "U1") (pin "44") (pinfunction "PH3_44") (pintype "passive+no_connect"))
    )
    (net (code "110") (name "unconnected-(U1A-PH6-Pad83)") (class "Default")
      (node (ref "U1") (pin "83") (pinfunction "PH6_83") (pintype "passive+no_connect"))
    )
    (net (code "111") (name "unconnected-(U1A-PH7-Pad84)") (class "Default")
      (node (ref "U1") (pin "84") (pinfunction "PH7_84") (pintype "passive+no_connect"))
    )
    (net (code "112") (name "unconnected-(U1A-PH8-Pad85)") (class "Default")
      (node (ref "U1") (pin "85") (pinfunction "PH8_85") (pintype "passive+no_connect"))
    )
    (net (code "113") (name "unconnected-(U1A-PH9-Pad86)") (class "Default")
      (node (ref "U1") (pin "86") (pinfunction "PH9_86") (pintype "passive+no_connect"))
    )
    (net (code "114") (name "unconnected-(U1A-PH10-Pad87)") (class "Default")
      (node (ref "U1") (pin "87") (pinfunction "PH10_87") (pintype "passive+no_connect"))
    )
    (net (code "115") (name "unconnected-(U1A-PH11-Pad88)") (class "Default")
      (node (ref "U1") (pin "88") (pinfunction "PH11_88") (pintype "passive+no_connect"))
    )
    (net (code "116") (name "unconnected-(U1A-PH12-Pad89)") (class "Default")
      (node (ref "U1") (pin "89") (pinfunction "PH12_89") (pintype "passive+no_connect"))
    )
    (net (code "117") (name "unconnected-(U1A-PI9-Pad11)") (class "Default")
      (node (ref "U1") (pin "11") (pinfunction "PI9_11") (pintype "passive+no_connect"))
    )
    (net (code "118") (name "unconnected-(U1A-PI10-Pad12)") (class "Default")
      (node (ref "U1") (pin "12") (pinfunction "PI10_12") (pintype "passive+no_connect"))
    )
    (net (code "119") (name "unconnected-(U1A-PI11-Pad13)") (class "Default")
      (node (ref "U1") (pin "13") (pinfunction "PI11_13") (pintype "passive+no_connect"))
    )
    (net (code "120") (name "unconnected-(U1B-PA8-Pad119)") (class "Default")
      (node (ref "U1") (pin "119") (pinfunction "PA8_119") (pintype "passive+no_connect"))
    )
    (net (code "121") (name "unconnected-(U1B-PB4-Pad162)") (class "Default")
      (node (ref "U1") (pin "162") (pinfunction "PB4_162") (pintype "passive+no_connect"))
    )
    (net (code "122") (name "unconnected-(U1B-PB5-Pad163)") (class "Default")
      (node (ref "U1") (pin "163") (pinfunction "PB5_163") (pintype "passive+no_connect"))
    )
    (net (code "123") (name "unconnected-(U1B-PC6-Pad115)") (class "Default")
      (node (ref "U1") (pin "115") (pinfunction "PC6_115") (pintype "passive+no_connect"))
    )
    (net (code "124") (name "unconnected-(U1B-PC7-Pad116)") (class "Default")
      (node (ref "U1") (pin "116") (pinfunction "PC7_116") (pintype "passive+no_connect"))
    )
    (net (code "125") (name "unconnected-(U1B-PC8-Pad117)") (class "Default")
      (node (ref "U1") (pin "117") (pinfunction "PC8_117") (pintype "passive+no_connect"))
    )
    (net (code "126") (name "unconnected-(U1B-PC9-Pad118)") (class "Default")
      (node (ref "U1") (pin "118") (pinfunction "PC9_118") (pintype "passive+no_connect"))
    )
    (net (code "127") (name "unconnected-(U1B-PD2-Pad144)") (class "Default")
      (node (ref "U1") (pin "144") (pinfunction "PD2_144") (pintype "passive+no_connect"))
    )
    (net (code "128") (name "unconnected-(U1B-PD3-Pad145)") (class "Default")
      (node (ref "U1") (pin "145") (pinfunction "PD3_145") (pintype "passive+no_connect"))
    )
    (net (code "129") (name "unconnected-(U1B-PD6-Pad150)") (class "Default")
      (node (ref "U1") (pin "150") (pinfunction "PD6_150") (pintype "passive+no_connect"))
    )
    (net (code "130") (name "unconnected-(U1B-PD13-Pad101)") (class "Default")
      (node (ref "U1") (pin "101") (pinfunction "PD13_101") (pintype "passive+no_connect"))
    )
    (net (code "131") (name "unconnected-(U1B-PE0-Pad169)") (class "Default")
      (node (ref "U1") (pin "169") (pinfunction "PE0_169") (pintype "passive+no_connect"))
    )
    (net (code "132") (name "unconnected-(U1B-PE1-Pad170)") (class "Default")
      (node (ref "U1") (pin "170") (pinfunction "PE1_170") (pintype "passive+no_connect"))
    )
    (net (code "133") (name "unconnected-(U1B-PG6-Pad110)") (class "Default")
      (node (ref "U1") (pin "110") (pinfunction "PG6_110") (pintype "passive+no_connect"))
    )
    (net (code "134") (name "unconnected-(U1B-PG7-Pad111)") (class "Default")
      (node (ref "U1") (pin "111") (pinfunction "PG7_111") (pintype "passive+no_connect"))
    )
    (net (code "135") (name "unconnected-(U1B-PG8-Pad112)") (class "Default")
      (node (ref "U1") (pin "112") (pinfunction "PG8_112") (pintype "passive+no_connect"))
    )
    (net (code "136") (name "unconnected-(U1B-PG9-Pad152)") (class "Default")
      (node (ref "U1") (pin "152") (pinfunction "PG9_152") (pintype "passive+no_connect"))
    )
    (net (code "137") (name "unconnected-(U1B-PG10-Pad153)") (class "Default")
      (node (ref "U1") (pin "153") (pinfunction "PG10_153") (pintype "passive+no_connect"))
    )
    (net (code "138") (name "unconnected-(U1B-PG15-Pad160)") (class "Default")
      (node (ref "U1") (pin "160") (pinfunction "PG15_160") (pintype "passive+no_connect"))
    )
    (net (code "139") (name "unconnected-(U1B-PH13-Pad128)") (class "Default")
      (node (ref "U1") (pin "128") (pinfunction "PH13_128") (pintype "passive+no_connect"))
    )
    (net (code "140") (name "unconnected-(U1B-PH14-Pad129)") (class "Default")
      (node (ref "U1") (pin "129") (pinfunction "PH14_129") (pintype "passive+no_connect"))
    )
    (net (code "141") (name "unconnected-(U1B-PI4-Pad173)") (class "Default")
      (node (ref "U1") (pin "173") (pinfunction "PI4_173") (pintype "passive+no_connect"))
    )
    (net (code "142") (name "unconnected-(U1B-PI5-Pad174)") (class "Default")
      (node (ref "U1") (pin "174") (pinfunction "PI5_174") (pintype "passive+no_connect"))
    )
    (net (code "143") (name "unconnected-(U1B-PI6-Pad175)") (class "Default")
      (node (ref "U1") (pin "175") (pinfunction "PI6_175") (pintype "passive+no_connect"))
    )
    (net (code "144") (name "unconnected-(U1B-PI7-Pad176)") (class "Default")
      (node (ref "U1") (pin "176") (pinfunction "PI7_176") (pintype "passive+no_connect"))
    )
    (net (code "145") (name "unconnected-(U1C-PC13{slash}ANTI_TAMP-Pad8)") (class "Default")
      (node (ref "U1") (pin "8") (pinfunction "PC13/ANTI_TAMP_8") (pintype "passive+no_connect"))
    )
    (net (code "146") (name "unconnected-(U1C-PI8{slash}ANTI_TAMP_2-Pad7)") (class "Default")
      (node (ref "U1") (pin "7") (pinfunction "PI8/ANTI_TAMP_2_7") (pintype "passive+no_connect"))
    )
  )
)
